# uven2-mk3-main-board.net
KiCad netlist of a schematic drawn in EasyEDA Pro
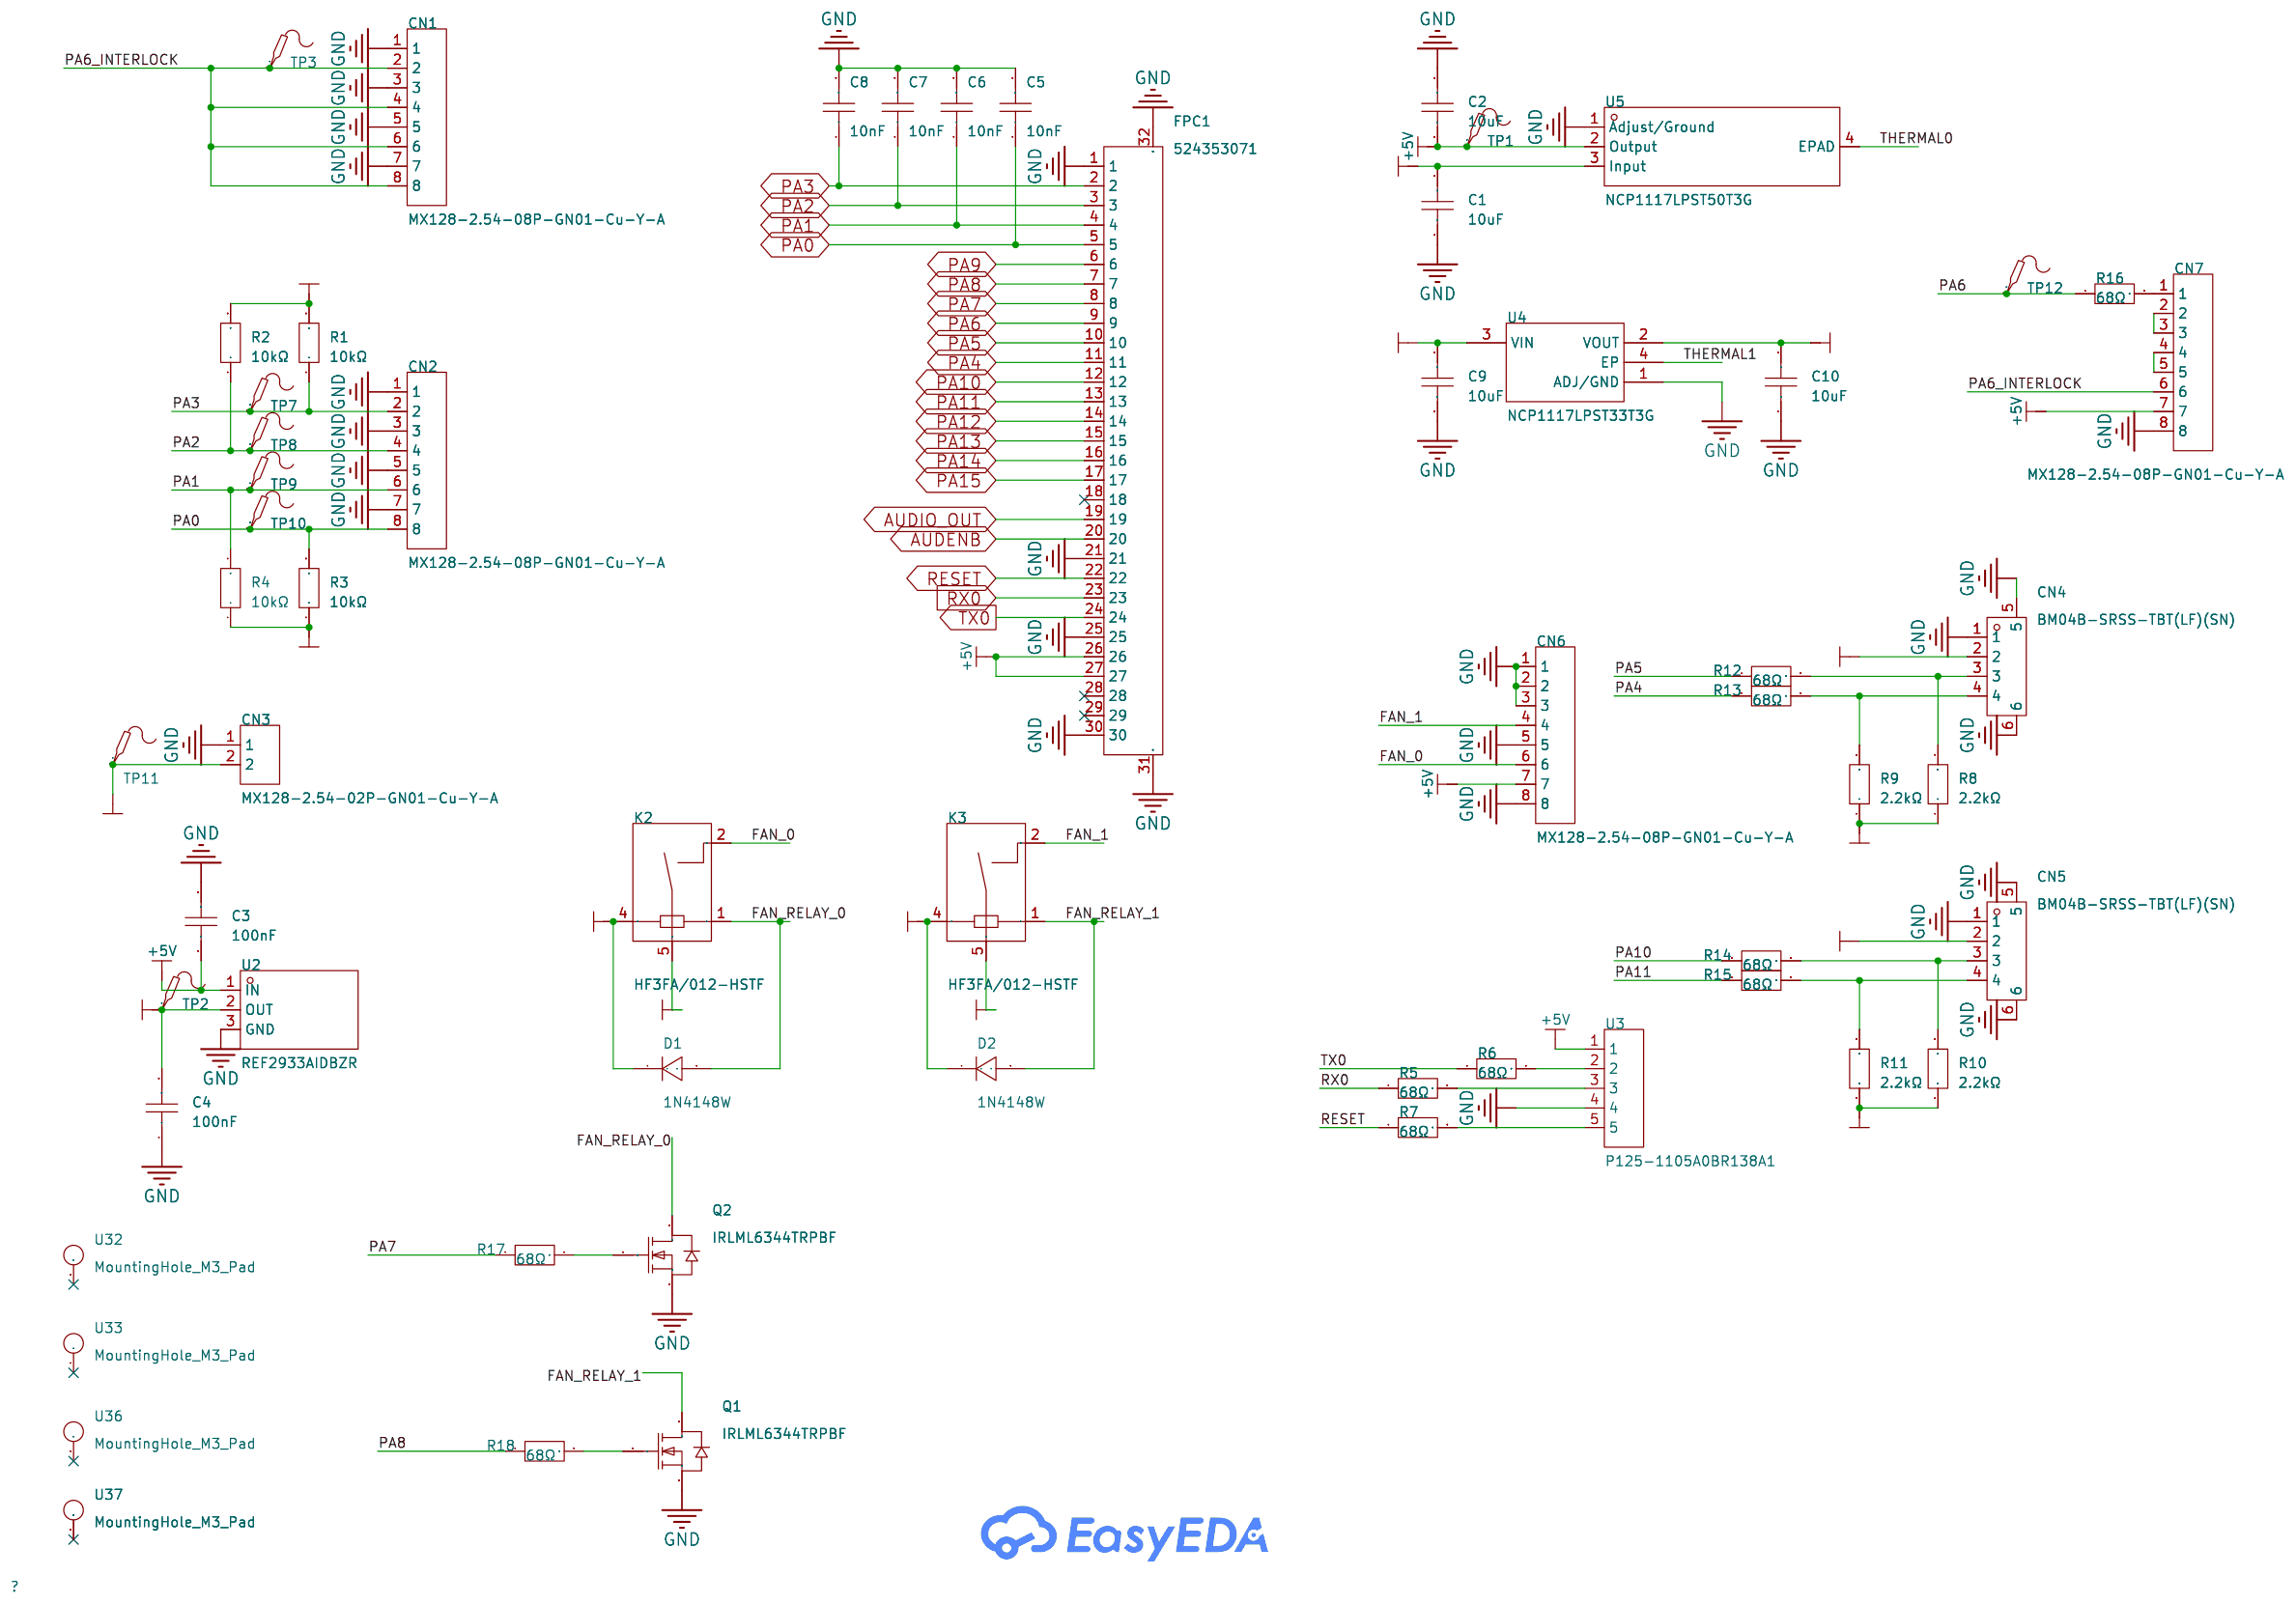
[diagram p0: schematic sheet]

(export (version "E")
  (design (tool "Eeschema 10.0.6"))
  (components
    (comp (ref "C1")
      (value "10uF")
      (footprint "easyedapro:C0805")
      (description "Capacitance:10uF Tolerance:±10% Tolerance:±10% Voltage Rating:25V Temperature Coefficient:X5R")
      (fields
        (field (name "Manufacturer Part") "FCC0805X106K250FT")
        (field (name "Manufacturer") "FOJAN(富捷)")
      )
      (libsource (lib "easyedapro") (part "FCC0805X106K250FT"))
    )
    (comp (ref "C2")
      (value "10uF")
      (footprint "easyedapro:C0805")
      (description "Capacitance:10uF Tolerance:±10% Tolerance:±10% Voltage Rating:25V Temperature Coefficient:X5R")
      (fields
        (field (name "Manufacturer Part") "FCC0805X106K250FT")
        (field (name "Manufacturer") "FOJAN(富捷)")
      )
      (libsource (lib "easyedapro") (part "FCC0805X106K250FT"))
    )
    (comp (ref "C3")
      (value "100nF")
      (footprint "easyedapro:C0603")
      (description "Capacitance:100nF Tolerance:±10% Tolerance:±10% Voltage Rating:16V Temperature Coefficient:X7R")
      (fields (field (name "Manufacturer Part") "C0603C104K4RACTU") (field (name "Manufacturer") "KEMET(基美)"))
      (libsource (lib "easyedapro") (part "C0603C104K4RACTU"))
    )
    (comp (ref "C4")
      (value "100nF")
      (footprint "easyedapro:C0603")
      (description "Capacitance:100nF Tolerance:±10% Tolerance:±10% Voltage Rating:16V Temperature Coefficient:X7R")
      (fields (field (name "Manufacturer Part") "C0603C104K4RACTU") (field (name "Manufacturer") "KEMET(基美)"))
      (libsource (lib "easyedapro") (part "C0603C104K4RACTU"))
    )
    (comp (ref "C5")
      (value "10nF")
      (footprint "easyedapro:C0402")
      (description "Capacitance:10nF Tolerance:±10% Tolerance:±10% Voltage Rating:16V Temperature Coefficient:X7R")
      (fields
        (field (name "Manufacturer Part") "GRT155R71C103KE01D")
        (field (name "Manufacturer") "muRata(村田)")
      )
      (libsource (lib "easyedapro") (part "GRT155R71C103KE01D"))
    )
    (comp (ref "C6")
      (value "10nF")
      (footprint "easyedapro:C0402")
      (description "Capacitance:10nF Tolerance:±10% Tolerance:±10% Voltage Rating:16V Temperature Coefficient:X7R")
      (fields
        (field (name "Manufacturer Part") "GRT155R71C103KE01D")
        (field (name "Manufacturer") "muRata(村田)")
      )
      (libsource (lib "easyedapro") (part "GRT155R71C103KE01D"))
    )
    (comp (ref "C7")
      (value "10nF")
      (footprint "easyedapro:C0402")
      (description "Capacitance:10nF Tolerance:±10% Tolerance:±10% Voltage Rating:16V Temperature Coefficient:X7R")
      (fields
        (field (name "Manufacturer Part") "GRT155R71C103KE01D")
        (field (name "Manufacturer") "muRata(村田)")
      )
      (libsource (lib "easyedapro") (part "GRT155R71C103KE01D"))
    )
    (comp (ref "C8")
      (value "10nF")
      (footprint "easyedapro:C0402")
      (description "Capacitance:10nF Tolerance:±10% Tolerance:±10% Voltage Rating:16V Temperature Coefficient:X7R")
      (fields
        (field (name "Manufacturer Part") "GRT155R71C103KE01D")
        (field (name "Manufacturer") "muRata(村田)")
      )
      (libsource (lib "easyedapro") (part "GRT155R71C103KE01D"))
    )
    (comp (ref "C9")
      (value "10uF")
      (footprint "easyedapro:C0805")
      (description "Capacitance:10uF Tolerance:±10% Tolerance:±10% Voltage Rating:25V Temperature Coefficient:X5R")
      (fields
        (field (name "Manufacturer Part") "FCC0805X106K250FT")
        (field (name "Manufacturer") "FOJAN(富捷)")
      )
      (libsource (lib "easyedapro") (part "FCC0805X106K250FT"))
    )
    (comp (ref "C10")
      (value "10uF")
      (footprint "easyedapro:C0805")
      (description "Capacitance:10uF Tolerance:±10% Tolerance:±10% Voltage Rating:25V Temperature Coefficient:X5R")
      (fields
        (field (name "Manufacturer Part") "FCC0805X106K250FT")
        (field (name "Manufacturer") "FOJAN(富捷)")
      )
      (libsource (lib "easyedapro") (part "FCC0805X106K250FT"))
    )
    (comp (ref "CN1")
      (value "MX128-2.54-08P-GN01-Cu-Y-A")
      (footprint "easyedapro:CONN-TH_8P-P2.54_MX128-2.54-GN01-08P-CU-Y-A")
      (fields (field (name "Manufacturer") "MAX(迈旭)"))
      (libsource (lib "easyedapro") (part "MX128-2.54-08P-GN01-CU-Y-A"))
    )
    (comp (ref "CN2")
      (value "MX128-2.54-08P-GN01-Cu-Y-A")
      (footprint "easyedapro:CONN-TH_8P-P2.54_MX128-2.54-GN01-08P-CU-Y-A")
      (fields (field (name "Manufacturer") "MAX(迈旭)"))
      (libsource (lib "easyedapro") (part "MX128-2.54-08P-GN01-CU-Y-A"))
    )
    (comp (ref "CN3")
      (value "MX128-2.54-02P-GN01-Cu-Y-A")
      (footprint "easyedapro:CONN-TH_2P-P2.54_MX128-2.54-GN01-02P-CU-Y-A")
      (fields (field (name "Manufacturer") "MAX(迈旭)"))
      (libsource (lib "easyedapro") (part "MX128-2.54-02P-GN01-CU-Y-A"))
    )
    (comp (ref "CN4")
      (value "BM04B-SRSS-TBT(LF)(SN)")
      (footprint "easyedapro:CONN-SMD_BM04B-SRSS-TBT-LF-SN")
      (fields (field (name "Manufacturer") "JST"))
      (libsource (lib "easyedapro") (part "BM04B-SRSS-TBT(LF)(SN)"))
    )
    (comp (ref "CN5")
      (value "BM04B-SRSS-TBT(LF)(SN)")
      (footprint "easyedapro:CONN-SMD_BM04B-SRSS-TBT-LF-SN")
      (fields (field (name "Manufacturer") "JST"))
      (libsource (lib "easyedapro") (part "BM04B-SRSS-TBT(LF)(SN)"))
    )
    (comp (ref "CN6")
      (value "MX128-2.54-08P-GN01-Cu-Y-A")
      (footprint "easyedapro:CONN-TH_8P-P2.54_MX128-2.54-GN01-08P-CU-Y-A")
      (fields (field (name "Manufacturer") "MAX(迈旭)"))
      (libsource (lib "easyedapro") (part "MX128-2.54-08P-GN01-CU-Y-A"))
    )
    (comp (ref "CN7")
      (value "MX128-2.54-08P-GN01-Cu-Y-A")
      (footprint "easyedapro:CONN-TH_8P-P2.54_MX128-2.54-GN01-08P-CU-Y-A")
      (fields (field (name "Manufacturer") "MAX(迈旭)"))
      (libsource (lib "easyedapro") (part "MX128-2.54-08P-GN01-CU-Y-A"))
    )
    (comp (ref "D1")
      (value "1N4148W")
      (footprint "easyedapro:SOD-123F_L2.7-W1.6-LS3.8-RD")
      (fields (field (name "Manufacturer") "ST(先科)"))
      (libsource (lib "easyedapro") (part "1N4148W_C81598"))
    )
    (comp (ref "D2")
      (value "1N4148W")
      (footprint "easyedapro:SOD-123F_L2.7-W1.6-LS3.8-RD")
      (fields (field (name "Manufacturer") "ST(先科)"))
      (libsource (lib "easyedapro") (part "1N4148W_C81598"))
    )
    (comp (ref "FPC1")
      (value "524353071")
      (footprint "easyedapro:FPC-SMD_P0.50-30P_1X30P")
      (fields (field (name "Manufacturer") "MOLEX"))
      (libsource (lib "easyedapro") (part "0524353071"))
    )
    (comp (ref "K2")
      (value "HF3FA/012-HSTF")
      (footprint "easyedapro:RELAY-TH_HF3FA-XX-HXX-XXX")
      (fields (field (name "Manufacturer") "HF(宏发)"))
      (libsource (lib "easyedapro") (part "HF3FA/012-HSTF"))
    )
    (comp (ref "K3")
      (value "HF3FA/012-HSTF")
      (footprint "easyedapro:RELAY-TH_HF3FA-XX-HXX-XXX")
      (fields (field (name "Manufacturer") "HF(宏发)"))
      (libsource (lib "easyedapro") (part "HF3FA/012-HSTF"))
    )
    (comp (ref "Q1")
      (value "IRLML6344TRPBF")
      (footprint "easyedapro:SOT-23-3_L2.9-W1.6-P1.90-LS2.8-BR")
      (fields (field (name "Manufacturer") "Infineon(英飞凌)"))
      (libsource (lib "easyedapro") (part "IRLML6344TRPBF"))
    )
    (comp (ref "Q2")
      (value "IRLML6344TRPBF")
      (footprint "easyedapro:SOT-23-3_L2.9-W1.6-P1.90-LS2.8-BR")
      (fields (field (name "Manufacturer") "Infineon(英飞凌)"))
      (libsource (lib "easyedapro") (part "IRLML6344TRPBF"))
    )
    (comp (ref "R1")
      (value "10kΩ")
      (footprint "easyedapro:R0603")
      (description "Resistance:10kΩ Tolerance:±1% Tolerance:±1% Power(Watts):100mW")
      (fields (field (name "Manufacturer Part") "RCA0310KFLF") (field (name "Manufacturer") "HKR(香港电阻)"))
      (libsource (lib "easyedapro") (part "RCA0310KFLF"))
    )
    (comp (ref "R2")
      (value "10kΩ")
      (footprint "easyedapro:R0603")
      (description "Resistance:10kΩ Tolerance:±1% Tolerance:±1% Power(Watts):100mW")
      (fields (field (name "Manufacturer Part") "RCA0310KFLF") (field (name "Manufacturer") "HKR(香港电阻)"))
      (libsource (lib "easyedapro") (part "RCA0310KFLF"))
    )
    (comp (ref "R3")
      (value "10kΩ")
      (footprint "easyedapro:R0603")
      (description "Resistance:10kΩ Tolerance:±1% Tolerance:±1% Power(Watts):100mW")
      (fields (field (name "Manufacturer Part") "RCA0310KFLF") (field (name "Manufacturer") "HKR(香港电阻)"))
      (libsource (lib "easyedapro") (part "RCA0310KFLF"))
    )
    (comp (ref "R4")
      (value "10kΩ")
      (footprint "easyedapro:R0603")
      (description "Resistance:10kΩ Tolerance:±1% Tolerance:±1% Power(Watts):100mW")
      (fields (field (name "Manufacturer Part") "RCA0310KFLF") (field (name "Manufacturer") "HKR(香港电阻)"))
      (libsource (lib "easyedapro") (part "RCA0310KFLF"))
    )
    (comp (ref "R5")
      (value "68Ω")
      (footprint "easyedapro:R0402")
      (fields (field (name "Manufacturer Part") "FRC0402F68R0TS") (field (name "Manufacturer") "FOJAN(富捷)"))
      (libsource (lib "easyedapro") (part "FRC0402F68R0TS"))
    )
    (comp (ref "R6")
      (value "68Ω")
      (footprint "easyedapro:R0402")
      (fields (field (name "Manufacturer Part") "FRC0402F68R0TS") (field (name "Manufacturer") "FOJAN(富捷)"))
      (libsource (lib "easyedapro") (part "FRC0402F68R0TS"))
    )
    (comp (ref "R7")
      (value "68Ω")
      (footprint "easyedapro:R0402")
      (fields (field (name "Manufacturer Part") "FRC0402F68R0TS") (field (name "Manufacturer") "FOJAN(富捷)"))
      (libsource (lib "easyedapro") (part "FRC0402F68R0TS"))
    )
    (comp (ref "R8")
      (value "2.2kΩ")
      (footprint "easyedapro:R0402")
      (fields (field (name "Manufacturer Part") "FRC0402J222 TS") (field (name "Manufacturer") "FOJAN(富捷)"))
      (libsource (lib "easyedapro") (part "FRC0402J222 TS"))
    )
    (comp (ref "R9")
      (value "2.2kΩ")
      (footprint "easyedapro:R0402")
      (fields (field (name "Manufacturer Part") "FRC0402J222 TS") (field (name "Manufacturer") "FOJAN(富捷)"))
      (libsource (lib "easyedapro") (part "FRC0402J222 TS"))
    )
    (comp (ref "R10")
      (value "2.2kΩ")
      (footprint "easyedapro:R0402")
      (fields (field (name "Manufacturer Part") "FRC0402J222 TS") (field (name "Manufacturer") "FOJAN(富捷)"))
      (libsource (lib "easyedapro") (part "FRC0402J222 TS"))
    )
    (comp (ref "R11")
      (value "2.2kΩ")
      (footprint "easyedapro:R0402")
      (fields (field (name "Manufacturer Part") "FRC0402J222 TS") (field (name "Manufacturer") "FOJAN(富捷)"))
      (libsource (lib "easyedapro") (part "FRC0402J222 TS"))
    )
    (comp (ref "R12")
      (value "68Ω")
      (footprint "easyedapro:R0402")
      (fields (field (name "Manufacturer Part") "FRC0402F68R0TS") (field (name "Manufacturer") "FOJAN(富捷)"))
      (libsource (lib "easyedapro") (part "FRC0402F68R0TS"))
    )
    (comp (ref "R13")
      (value "68Ω")
      (footprint "easyedapro:R0402")
      (fields (field (name "Manufacturer Part") "FRC0402F68R0TS") (field (name "Manufacturer") "FOJAN(富捷)"))
      (libsource (lib "easyedapro") (part "FRC0402F68R0TS"))
    )
    (comp (ref "R14")
      (value "68Ω")
      (footprint "easyedapro:R0402")
      (fields (field (name "Manufacturer Part") "FRC0402F68R0TS") (field (name "Manufacturer") "FOJAN(富捷)"))
      (libsource (lib "easyedapro") (part "FRC0402F68R0TS"))
    )
    (comp (ref "R15")
      (value "68Ω")
      (footprint "easyedapro:R0402")
      (fields (field (name "Manufacturer Part") "FRC0402F68R0TS") (field (name "Manufacturer") "FOJAN(富捷)"))
      (libsource (lib "easyedapro") (part "FRC0402F68R0TS"))
    )
    (comp (ref "R16")
      (value "68Ω")
      (footprint "easyedapro:R0402")
      (fields (field (name "Manufacturer Part") "FRC0402F68R0TS") (field (name "Manufacturer") "FOJAN(富捷)"))
      (libsource (lib "easyedapro") (part "FRC0402F68R0TS"))
    )
    (comp (ref "R17")
      (value "68Ω")
      (footprint "easyedapro:R0402")
      (fields (field (name "Manufacturer Part") "FRC0402F68R0TS") (field (name "Manufacturer") "FOJAN(富捷)"))
      (libsource (lib "easyedapro") (part "FRC0402F68R0TS"))
    )
    (comp (ref "R18")
      (value "68Ω")
      (footprint "easyedapro:R0402")
      (fields (field (name "Manufacturer Part") "FRC0402F68R0TS") (field (name "Manufacturer") "FOJAN(富捷)"))
      (libsource (lib "easyedapro") (part "FRC0402F68R0TS"))
    )
    (comp (ref "TP1")
      (value "~")
      (footprint "easyedapro:Test-Point-0.5mm")
      (description "Test Point 测试点")
      (libsource (lib "easyedapro") (part "Test-Point"))
    )
    (comp (ref "TP2")
      (value "~")
      (footprint "easyedapro:Test-Point-0.5mm")
      (description "Test Point 测试点")
      (libsource (lib "easyedapro") (part "Test-Point"))
    )
    (comp (ref "TP3")
      (value "~")
      (footprint "easyedapro:Test-Point-0.5mm")
      (description "Test Point 测试点")
      (libsource (lib "easyedapro") (part "Test-Point"))
    )
    (comp (ref "TP7")
      (value "~")
      (footprint "easyedapro:Test-Point-0.5mm")
      (description "Test Point 测试点")
      (libsource (lib "easyedapro") (part "Test-Point"))
    )
    (comp (ref "TP8")
      (value "~")
      (footprint "easyedapro:Test-Point-0.5mm")
      (description "Test Point 测试点")
      (libsource (lib "easyedapro") (part "Test-Point"))
    )
    (comp (ref "TP9")
      (value "~")
      (footprint "easyedapro:Test-Point-0.5mm")
      (description "Test Point 测试点")
      (libsource (lib "easyedapro") (part "Test-Point"))
    )
    (comp (ref "TP10")
      (value "~")
      (footprint "easyedapro:Test-Point-0.5mm")
      (description "Test Point 测试点")
      (libsource (lib "easyedapro") (part "Test-Point"))
    )
    (comp (ref "TP11")
      (value "~")
      (footprint "easyedapro:Test-Point-0.5mm")
      (description "Test Point 测试点")
      (libsource (lib "easyedapro") (part "Test-Point"))
    )
    (comp (ref "TP12")
      (value "~")
      (footprint "easyedapro:Test-Point-0.5mm")
      (description "Test Point 测试点")
      (libsource (lib "easyedapro") (part "Test-Point"))
    )
    (comp (ref "U2")
      (value "REF2933AIDBZR")
      (footprint "easyedapro:SOT-23-3_L2.9-W1.3-P1.90-LS2.4-BR")
      (fields (field (name "Manufacturer") "TI(德州仪器)"))
      (libsource (lib "easyedapro") (part "REF2933AIDBZR"))
    )
    (comp (ref "U3")
      (value "P125-1105A0BR138A1")
      (footprint "easyedapro:HDR-TH_5P-P2.54-H-M-W10.4")
      (fields (field (name "Manufacturer") "Yxcon(宇熙精密)"))
      (libsource (lib "easyedapro") (part "P125-1105A0BR138A1"))
    )
    (comp (ref "U4")
      (value "NCP1117LPST33T3G")
      (footprint "easyedapro:SOT-223_L6.5-W3.5-P2.30-LS7.0-BR")
      (fields (field (name "Manufacturer") "onsemi(安森美)"))
      (libsource (lib "easyedapro") (part "NCP1117LPST33T3G"))
    )
    (comp (ref "U5")
      (value "NCP1117LPST50T3G")
      (footprint "easyedapro:SOT-223_L6.5-W3.5-P2.30-LS7.0-BR")
      (fields (field (name "Manufacturer") "onsemi(安森美)"))
      (libsource (lib "easyedapro") (part "NCP1117LPST50T3G"))
    )
    (comp (ref "U32")
      (value "MountingHole_M3_Pad")
      (footprint "easyedapro:MountingHole_3.2mm_M3_DIN965_Pad_TopOnly")
      (libsource (lib "easyedapro") (part "Mounting_M3_Hole_Pad"))
    )
    (comp (ref "U33")
      (value "MountingHole_M3_Pad")
      (footprint "easyedapro:MountingHole_3.2mm_M3_DIN965_Pad_TopOnly")
      (libsource (lib "easyedapro") (part "Mounting_M3_Hole_Pad"))
    )
    (comp (ref "U36")
      (value "MountingHole_M3_Pad")
      (footprint "easyedapro:MountingHole_3.2mm_M3_DIN965_Pad_TopOnly")
      (libsource (lib "easyedapro") (part "Mounting_M3_Hole_Pad"))
    )
    (comp (ref "U37")
      (value "MountingHole_M3_Pad")
      (footprint "easyedapro:MountingHole_3.2mm_M3_DIN965_Pad_TopOnly")
      (libsource (lib "easyedapro") (part "Mounting_M3_Hole_Pad"))
    )
  )
  (nets
    (net (code "1") (name "+3.3V") (class "Default")
      (node (ref "C10") (pin "2") (pinfunction "2_2") (pintype "unspecified"))
      (node (ref "CN4") (pin "2") (pinfunction "2_2") (pintype "unspecified"))
      (node (ref "CN5") (pin "2") (pinfunction "2_2") (pintype "unspecified"))
      (node (ref "R10") (pin "1") (pinfunction "1_1") (pintype "unspecified"))
      (node (ref "R11") (pin "1") (pinfunction "1_1") (pintype "unspecified"))
      (node (ref "R8") (pin "1") (pinfunction "1_1") (pintype "unspecified"))
      (node (ref "R9") (pin "1") (pinfunction "1_1") (pintype "unspecified"))
      (node (ref "U4") (pin "2") (pinfunction "VOUT_2") (pintype "unspecified"))
    )
    (net (code "2") (name "+3.3VREF") (class "Default")
      (node (ref "C4") (pin "2") (pinfunction "2_2") (pintype "unspecified"))
      (node (ref "R1") (pin "2") (pinfunction "2_2") (pintype "unspecified"))
      (node (ref "R2") (pin "2") (pinfunction "2_2") (pintype "unspecified"))
      (node (ref "R3") (pin "1") (pinfunction "1_1") (pintype "unspecified"))
      (node (ref "R4") (pin "1") (pinfunction "1_1") (pintype "unspecified"))
      (node (ref "TP2") (pin "1") (pinfunction "1_1") (pintype "unspecified"))
      (node (ref "U2") (pin "2") (pinfunction "OUT_2") (pintype "unspecified"))
    )
    (net (code "3") (name "+5V") (class "Default")
      (node (ref "C2") (pin "2") (pinfunction "2_2") (pintype "unspecified"))
      (node (ref "C3") (pin "1") (pinfunction "1_1") (pintype "unspecified"))
      (node (ref "CN6") (pin "7") (pinfunction "7_7") (pintype "unspecified"))
      (node (ref "CN7") (pin "7") (pinfunction "7_7") (pintype "unspecified"))
      (node (ref "FPC1") (pin "26") (pinfunction "26_26") (pintype "unspecified"))
      (node (ref "FPC1") (pin "27") (pinfunction "27_27") (pintype "unspecified"))
      (node (ref "TP1") (pin "1") (pinfunction "1_1") (pintype "unspecified"))
      (node (ref "U2") (pin "1") (pinfunction "IN_1") (pintype "unspecified"))
      (node (ref "U3") (pin "1") (pinfunction "1_1") (pintype "unspecified"))
      (node (ref "U5") (pin "2") (pinfunction "Output_2") (pintype "unspecified"))
    )
    (net (code "4") (name "+12V") (class "Default")
      (node (ref "C1") (pin "2") (pinfunction "2_2") (pintype "unspecified"))
      (node (ref "C9") (pin "2") (pinfunction "2_2") (pintype "unspecified"))
      (node (ref "CN3") (pin "2") (pinfunction "2_2") (pintype "unspecified"))
      (node (ref "D1") (pin "1") (pinfunction "K_1") (pintype "unspecified"))
      (node (ref "D2") (pin "1") (pinfunction "K_1") (pintype "unspecified"))
      (node (ref "K2") (pin "4") (pinfunction "4_4") (pintype "input"))
      (node (ref "K2") (pin "5") (pinfunction "5_5") (pintype "input"))
      (node (ref "K3") (pin "4") (pinfunction "4_4") (pintype "input"))
      (node (ref "K3") (pin "5") (pinfunction "5_5") (pintype "input"))
      (node (ref "TP11") (pin "1") (pinfunction "1_1") (pintype "unspecified"))
      (node (ref "U4") (pin "3") (pinfunction "VIN_3") (pintype "unspecified"))
      (node (ref "U5") (pin "3") (pinfunction "Input_3") (pintype "unspecified"))
    )
    (net (code "5") (name "/FAN_0") (class "Default")
      (node (ref "CN6") (pin "6") (pinfunction "6_6") (pintype "unspecified"))
      (node (ref "K2") (pin "2") (pinfunction "2_2") (pintype "input"))
    )
    (net (code "6") (name "/FAN_1") (class "Default")
      (node (ref "CN6") (pin "4") (pinfunction "4_4") (pintype "unspecified"))
      (node (ref "K3") (pin "2") (pinfunction "2_2") (pintype "input"))
    )
    (net (code "7") (name "/FAN_RELAY_0") (class "Default")
      (node (ref "D1") (pin "2") (pinfunction "A_2") (pintype "unspecified"))
      (node (ref "K2") (pin "1") (pinfunction "1_1") (pintype "input"))
      (node (ref "Q2") (pin "3") (pinfunction "D_3") (pintype "unspecified"))
    )
    (net (code "8") (name "/FAN_RELAY_1") (class "Default")
      (node (ref "D2") (pin "2") (pinfunction "A_2") (pintype "unspecified"))
      (node (ref "K3") (pin "1") (pinfunction "1_1") (pintype "input"))
      (node (ref "Q1") (pin "3") (pinfunction "D_3") (pintype "unspecified"))
    )
    (net (code "9") (name "/PA6_INTERLOCK") (class "Default")
      (node (ref "CN1") (pin "2") (pinfunction "2_2") (pintype "unspecified"))
      (node (ref "CN1") (pin "4") (pinfunction "4_4") (pintype "unspecified"))
      (node (ref "CN1") (pin "6") (pinfunction "6_6") (pintype "unspecified"))
      (node (ref "CN1") (pin "8") (pinfunction "8_8") (pintype "unspecified"))
      (node (ref "CN7") (pin "6") (pinfunction "6_6") (pintype "unspecified"))
      (node (ref "TP3") (pin "1") (pinfunction "1_1") (pintype "unspecified"))
    )
    (net (code "10") (name "/THERMAL0") (class "Default")
      (node (ref "U5") (pin "4") (pinfunction "EPAD_4") (pintype "unspecified"))
    )
    (net (code "11") (name "/THERMAL1") (class "Default")
      (node (ref "U4") (pin "4") (pinfunction "EP_4") (pintype "unspecified"))
    )
    (net (code "12") (name "AUDENB") (class "Default")
      (node (ref "FPC1") (pin "20") (pinfunction "20_20") (pintype "unspecified"))
    )
    (net (code "13") (name "AUDIO_OUT") (class "Default")
      (node (ref "FPC1") (pin "19") (pinfunction "19_19") (pintype "unspecified"))
    )
    (net (code "14") (name "GND") (class "Default")
      (node (ref "C1") (pin "1") (pinfunction "1_1") (pintype "unspecified"))
      (node (ref "C10") (pin "1") (pinfunction "1_1") (pintype "unspecified"))
      (node (ref "C2") (pin "1") (pinfunction "1_1") (pintype "unspecified"))
      (node (ref "C3") (pin "2") (pinfunction "2_2") (pintype "unspecified"))
      (node (ref "C4") (pin "1") (pinfunction "1_1") (pintype "unspecified"))
      (node (ref "C5") (pin "2") (pinfunction "2_2") (pintype "unspecified"))
      (node (ref "C6") (pin "2") (pinfunction "2_2") (pintype "unspecified"))
      (node (ref "C7") (pin "2") (pinfunction "2_2") (pintype "unspecified"))
      (node (ref "C8") (pin "2") (pinfunction "2_2") (pintype "unspecified"))
      (node (ref "C9") (pin "1") (pinfunction "1_1") (pintype "unspecified"))
      (node (ref "CN1") (pin "1") (pinfunction "1_1") (pintype "unspecified"))
      (node (ref "CN1") (pin "3") (pinfunction "3_3") (pintype "unspecified"))
      (node (ref "CN1") (pin "5") (pinfunction "5_5") (pintype "unspecified"))
      (node (ref "CN1") (pin "7") (pinfunction "7_7") (pintype "unspecified"))
      (node (ref "CN2") (pin "1") (pinfunction "1_1") (pintype "unspecified"))
      (node (ref "CN2") (pin "3") (pinfunction "3_3") (pintype "unspecified"))
      (node (ref "CN2") (pin "5") (pinfunction "5_5") (pintype "unspecified"))
      (node (ref "CN2") (pin "7") (pinfunction "7_7") (pintype "unspecified"))
      (node (ref "CN3") (pin "1") (pinfunction "1_1") (pintype "unspecified"))
      (node (ref "CN4") (pin "1") (pinfunction "1_1") (pintype "unspecified"))
      (node (ref "CN4") (pin "5") (pinfunction "5_5") (pintype "unspecified"))
      (node (ref "CN4") (pin "6") (pinfunction "6_6") (pintype "unspecified"))
      (node (ref "CN5") (pin "1") (pinfunction "1_1") (pintype "unspecified"))
      (node (ref "CN5") (pin "5") (pinfunction "5_5") (pintype "unspecified"))
      (node (ref "CN5") (pin "6") (pinfunction "6_6") (pintype "unspecified"))
      (node (ref "CN6") (pin "1") (pinfunction "1_1") (pintype "unspecified"))
      (node (ref "CN6") (pin "2") (pinfunction "2_2") (pintype "unspecified"))
      (node (ref "CN6") (pin "3") (pinfunction "3_3") (pintype "unspecified"))
      (node (ref "CN6") (pin "5") (pinfunction "5_5") (pintype "unspecified"))
      (node (ref "CN6") (pin "8") (pinfunction "8_8") (pintype "unspecified"))
      (node (ref "CN7") (pin "8") (pinfunction "8_8") (pintype "unspecified"))
      (node (ref "FPC1") (pin "1") (pinfunction "1_1") (pintype "unspecified"))
      (node (ref "FPC1") (pin "21") (pinfunction "21_21") (pintype "unspecified"))
      (node (ref "FPC1") (pin "25") (pinfunction "25_25") (pintype "unspecified"))
      (node (ref "FPC1") (pin "30") (pinfunction "30_30") (pintype "unspecified"))
      (node (ref "FPC1") (pin "31") (pinfunction "31_31") (pintype "unspecified"))
      (node (ref "FPC1") (pin "32") (pinfunction "32_32") (pintype "unspecified"))
      (node (ref "Q1") (pin "2") (pinfunction "S_2") (pintype "unspecified"))
      (node (ref "Q2") (pin "2") (pinfunction "S_2") (pintype "unspecified"))
      (node (ref "U2") (pin "3") (pinfunction "GND_3") (pintype "unspecified"))
      (node (ref "U3") (pin "4") (pinfunction "4_4") (pintype "unspecified"))
      (node (ref "U4") (pin "1") (pinfunction "ADJ/GND_1") (pintype "unspecified"))
      (node (ref "U5") (pin "1") (pinfunction "Adjust/Ground_1") (pintype "unspecified"))
    )
    (net (code "15") (name "Net-(CN4-Pad3)") (class "Default")
      (node (ref "CN4") (pin "3") (pinfunction "3_3") (pintype "unspecified"))
      (node (ref "R12") (pin "2") (pinfunction "2_2") (pintype "unspecified"))
      (node (ref "R8") (pin "2") (pinfunction "2_2") (pintype "unspecified"))
    )
    (net (code "16") (name "Net-(CN4-Pad4)") (class "Default")
      (node (ref "CN4") (pin "4") (pinfunction "4_4") (pintype "unspecified"))
      (node (ref "R13") (pin "2") (pinfunction "2_2") (pintype "unspecified"))
      (node (ref "R9") (pin "2") (pinfunction "2_2") (pintype "unspecified"))
    )
    (net (code "17") (name "Net-(CN5-Pad3)") (class "Default")
      (node (ref "CN5") (pin "3") (pinfunction "3_3") (pintype "unspecified"))
      (node (ref "R10") (pin "2") (pinfunction "2_2") (pintype "unspecified"))
      (node (ref "R14") (pin "2") (pinfunction "2_2") (pintype "unspecified"))
    )
    (net (code "18") (name "Net-(CN5-Pad4)") (class "Default")
      (node (ref "CN5") (pin "4") (pinfunction "4_4") (pintype "unspecified"))
      (node (ref "R11") (pin "2") (pinfunction "2_2") (pintype "unspecified"))
      (node (ref "R15") (pin "2") (pinfunction "2_2") (pintype "unspecified"))
    )
    (net (code "19") (name "Net-(CN7-Pad1)") (class "Default")
      (node (ref "CN7") (pin "1") (pinfunction "1_1") (pintype "unspecified"))
      (node (ref "R16") (pin "2") (pinfunction "2_2") (pintype "unspecified"))
    )
    (net (code "20") (name "Net-(CN7-Pad2)") (class "Default")
      (node (ref "CN7") (pin "2") (pinfunction "2_2") (pintype "unspecified"))
      (node (ref "CN7") (pin "3") (pinfunction "3_3") (pintype "unspecified"))
    )
    (net (code "21") (name "Net-(CN7-Pad4)") (class "Default")
      (node (ref "CN7") (pin "4") (pinfunction "4_4") (pintype "unspecified"))
      (node (ref "CN7") (pin "5") (pinfunction "5_5") (pintype "unspecified"))
    )
    (net (code "22") (name "Net-(Q1-G)") (class "Default")
      (node (ref "Q1") (pin "1") (pinfunction "G_1") (pintype "unspecified"))
      (node (ref "R18") (pin "2") (pinfunction "2_2") (pintype "unspecified"))
    )
    (net (code "23") (name "Net-(Q2-G)") (class "Default")
      (node (ref "Q2") (pin "1") (pinfunction "G_1") (pintype "unspecified"))
      (node (ref "R17") (pin "2") (pinfunction "2_2") (pintype "unspecified"))
    )
    (net (code "24") (name "Net-(R5-Pad2)") (class "Default")
      (node (ref "R5") (pin "2") (pinfunction "2_2") (pintype "unspecified"))
      (node (ref "U3") (pin "3") (pinfunction "3_3") (pintype "unspecified"))
    )
    (net (code "25") (name "Net-(R6-Pad2)") (class "Default")
      (node (ref "R6") (pin "2") (pinfunction "2_2") (pintype "unspecified"))
      (node (ref "U3") (pin "2") (pinfunction "2_2") (pintype "unspecified"))
    )
    (net (code "26") (name "Net-(R7-Pad2)") (class "Default")
      (node (ref "R7") (pin "2") (pinfunction "2_2") (pintype "unspecified"))
      (node (ref "U3") (pin "5") (pinfunction "5_5") (pintype "unspecified"))
    )
    (net (code "27") (name "PA0") (class "Default")
      (node (ref "C5") (pin "1") (pinfunction "1_1") (pintype "unspecified"))
      (node (ref "CN2") (pin "8") (pinfunction "8_8") (pintype "unspecified"))
      (node (ref "FPC1") (pin "5") (pinfunction "5_5") (pintype "unspecified"))
      (node (ref "R3") (pin "2") (pinfunction "2_2") (pintype "unspecified"))
      (node (ref "TP10") (pin "1") (pinfunction "1_1") (pintype "unspecified"))
    )
    (net (code "28") (name "PA1") (class "Default")
      (node (ref "C6") (pin "1") (pinfunction "1_1") (pintype "unspecified"))
      (node (ref "CN2") (pin "6") (pinfunction "6_6") (pintype "unspecified"))
      (node (ref "FPC1") (pin "4") (pinfunction "4_4") (pintype "unspecified"))
      (node (ref "R4") (pin "2") (pinfunction "2_2") (pintype "unspecified"))
      (node (ref "TP9") (pin "1") (pinfunction "1_1") (pintype "unspecified"))
    )
    (net (code "29") (name "PA2") (class "Default")
      (node (ref "C7") (pin "1") (pinfunction "1_1") (pintype "unspecified"))
      (node (ref "CN2") (pin "4") (pinfunction "4_4") (pintype "unspecified"))
      (node (ref "FPC1") (pin "3") (pinfunction "3_3") (pintype "unspecified"))
      (node (ref "R2") (pin "1") (pinfunction "1_1") (pintype "unspecified"))
      (node (ref "TP8") (pin "1") (pinfunction "1_1") (pintype "unspecified"))
    )
    (net (code "30") (name "PA3") (class "Default")
      (node (ref "C8") (pin "1") (pinfunction "1_1") (pintype "unspecified"))
      (node (ref "CN2") (pin "2") (pinfunction "2_2") (pintype "unspecified"))
      (node (ref "FPC1") (pin "2") (pinfunction "2_2") (pintype "unspecified"))
      (node (ref "R1") (pin "1") (pinfunction "1_1") (pintype "unspecified"))
      (node (ref "TP7") (pin "1") (pinfunction "1_1") (pintype "unspecified"))
    )
    (net (code "31") (name "PA4") (class "Default")
      (node (ref "FPC1") (pin "11") (pinfunction "11_11") (pintype "unspecified"))
      (node (ref "R13") (pin "1") (pinfunction "1_1") (pintype "unspecified"))
    )
    (net (code "32") (name "PA5") (class "Default")
      (node (ref "FPC1") (pin "10") (pinfunction "10_10") (pintype "unspecified"))
      (node (ref "R12") (pin "1") (pinfunction "1_1") (pintype "unspecified"))
    )
    (net (code "33") (name "PA6") (class "Default")
      (node (ref "FPC1") (pin "9") (pinfunction "9_9") (pintype "unspecified"))
      (node (ref "R16") (pin "1") (pinfunction "1_1") (pintype "unspecified"))
      (node (ref "TP12") (pin "1") (pinfunction "1_1") (pintype "unspecified"))
    )
    (net (code "34") (name "PA7") (class "Default")
      (node (ref "FPC1") (pin "8") (pinfunction "8_8") (pintype "unspecified"))
      (node (ref "R17") (pin "1") (pinfunction "1_1") (pintype "unspecified"))
    )
    (net (code "35") (name "PA8") (class "Default")
      (node (ref "FPC1") (pin "7") (pinfunction "7_7") (pintype "unspecified"))
      (node (ref "R18") (pin "1") (pinfunction "1_1") (pintype "unspecified"))
    )
    (net (code "36") (name "PA9") (class "Default")
      (node (ref "FPC1") (pin "6") (pinfunction "6_6") (pintype "unspecified"))
    )
    (net (code "37") (name "PA10") (class "Default")
      (node (ref "FPC1") (pin "12") (pinfunction "12_12") (pintype "unspecified"))
      (node (ref "R14") (pin "1") (pinfunction "1_1") (pintype "unspecified"))
    )
    (net (code "38") (name "PA11") (class "Default")
      (node (ref "FPC1") (pin "13") (pinfunction "13_13") (pintype "unspecified"))
      (node (ref "R15") (pin "1") (pinfunction "1_1") (pintype "unspecified"))
    )
    (net (code "39") (name "PA12") (class "Default")
      (node (ref "FPC1") (pin "14") (pinfunction "14_14") (pintype "unspecified"))
    )
    (net (code "40") (name "PA13") (class "Default")
      (node (ref "FPC1") (pin "15") (pinfunction "15_15") (pintype "unspecified"))
    )
    (net (code "41") (name "PA14") (class "Default")
      (node (ref "FPC1") (pin "16") (pinfunction "16_16") (pintype "unspecified"))
    )
    (net (code "42") (name "PA15") (class "Default")
      (node (ref "FPC1") (pin "17") (pinfunction "17_17") (pintype "unspecified"))
    )
    (net (code "43") (name "RESET") (class "Default")
      (node (ref "FPC1") (pin "22") (pinfunction "22_22") (pintype "unspecified"))
      (node (ref "R7") (pin "1") (pinfunction "1_1") (pintype "unspecified"))
    )
    (net (code "44") (name "RX0") (class "Default")
      (node (ref "FPC1") (pin "23") (pinfunction "23_23") (pintype "unspecified"))
      (node (ref "R5") (pin "1") (pinfunction "1_1") (pintype "unspecified"))
    )
    (net (code "45") (name "TX0") (class "Default")
      (node (ref "FPC1") (pin "24") (pinfunction "24_24") (pintype "unspecified"))
      (node (ref "R6") (pin "1") (pinfunction "1_1") (pintype "unspecified"))
    )
    (net (code "46") (name "unconnected-(FPC1-Pad18)") (class "Default")
      (node (ref "FPC1") (pin "18") (pinfunction "18_18") (pintype "unspecified+no_connect"))
    )
    (net (code "47") (name "unconnected-(FPC1-Pad28)") (class "Default")
      (node (ref "FPC1") (pin "28") (pinfunction "28_28") (pintype "unspecified+no_connect"))
    )
    (net (code "48") (name "unconnected-(FPC1-Pad29)") (class "Default")
      (node (ref "FPC1") (pin "29") (pinfunction "29_29") (pintype "unspecified+no_connect"))
    )
    (net (code "49") (name "unconnected-(U32-Pad1)") (class "Default")
      (node (ref "U32") (pin "1") (pinfunction "1_1") (pintype "input+no_connect"))
    )
    (net (code "50") (name "unconnected-(U33-Pad1)") (class "Default")
      (node (ref "U33") (pin "1") (pinfunction "1_1") (pintype "input+no_connect"))
    )
    (net (code "51") (name "unconnected-(U36-Pad1)") (class "Default")
      (node (ref "U36") (pin "1") (pinfunction "1_1") (pintype "input+no_connect"))
    )
    (net (code "52") (name "unconnected-(U37-Pad1)") (class "Default")
      (node (ref "U37") (pin "1") (pinfunction "1_1") (pintype "input+no_connect"))
    )
  )
)
